# Updated_ADC.net
KiCad netlist of a schematic drawn in EAGLE
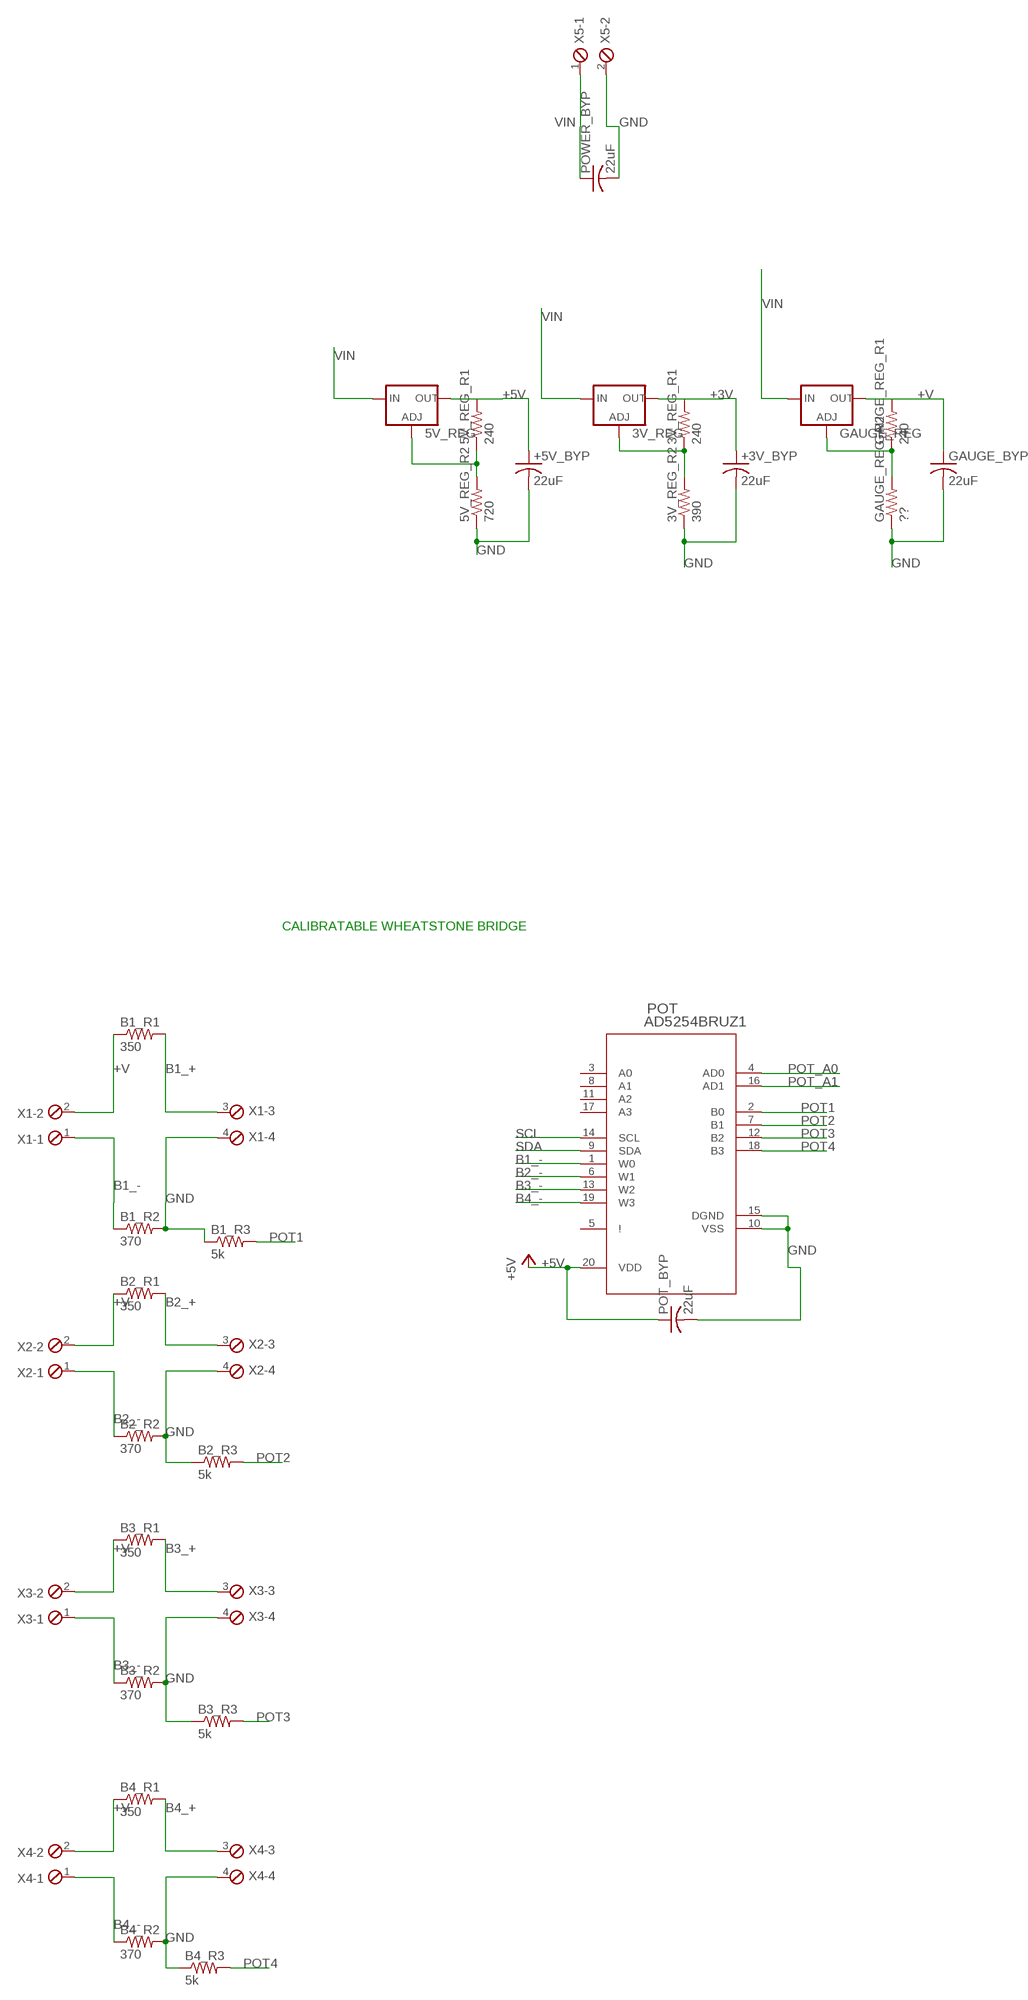
[diagram p0: schematic, sheet 1, part 1 of 2]
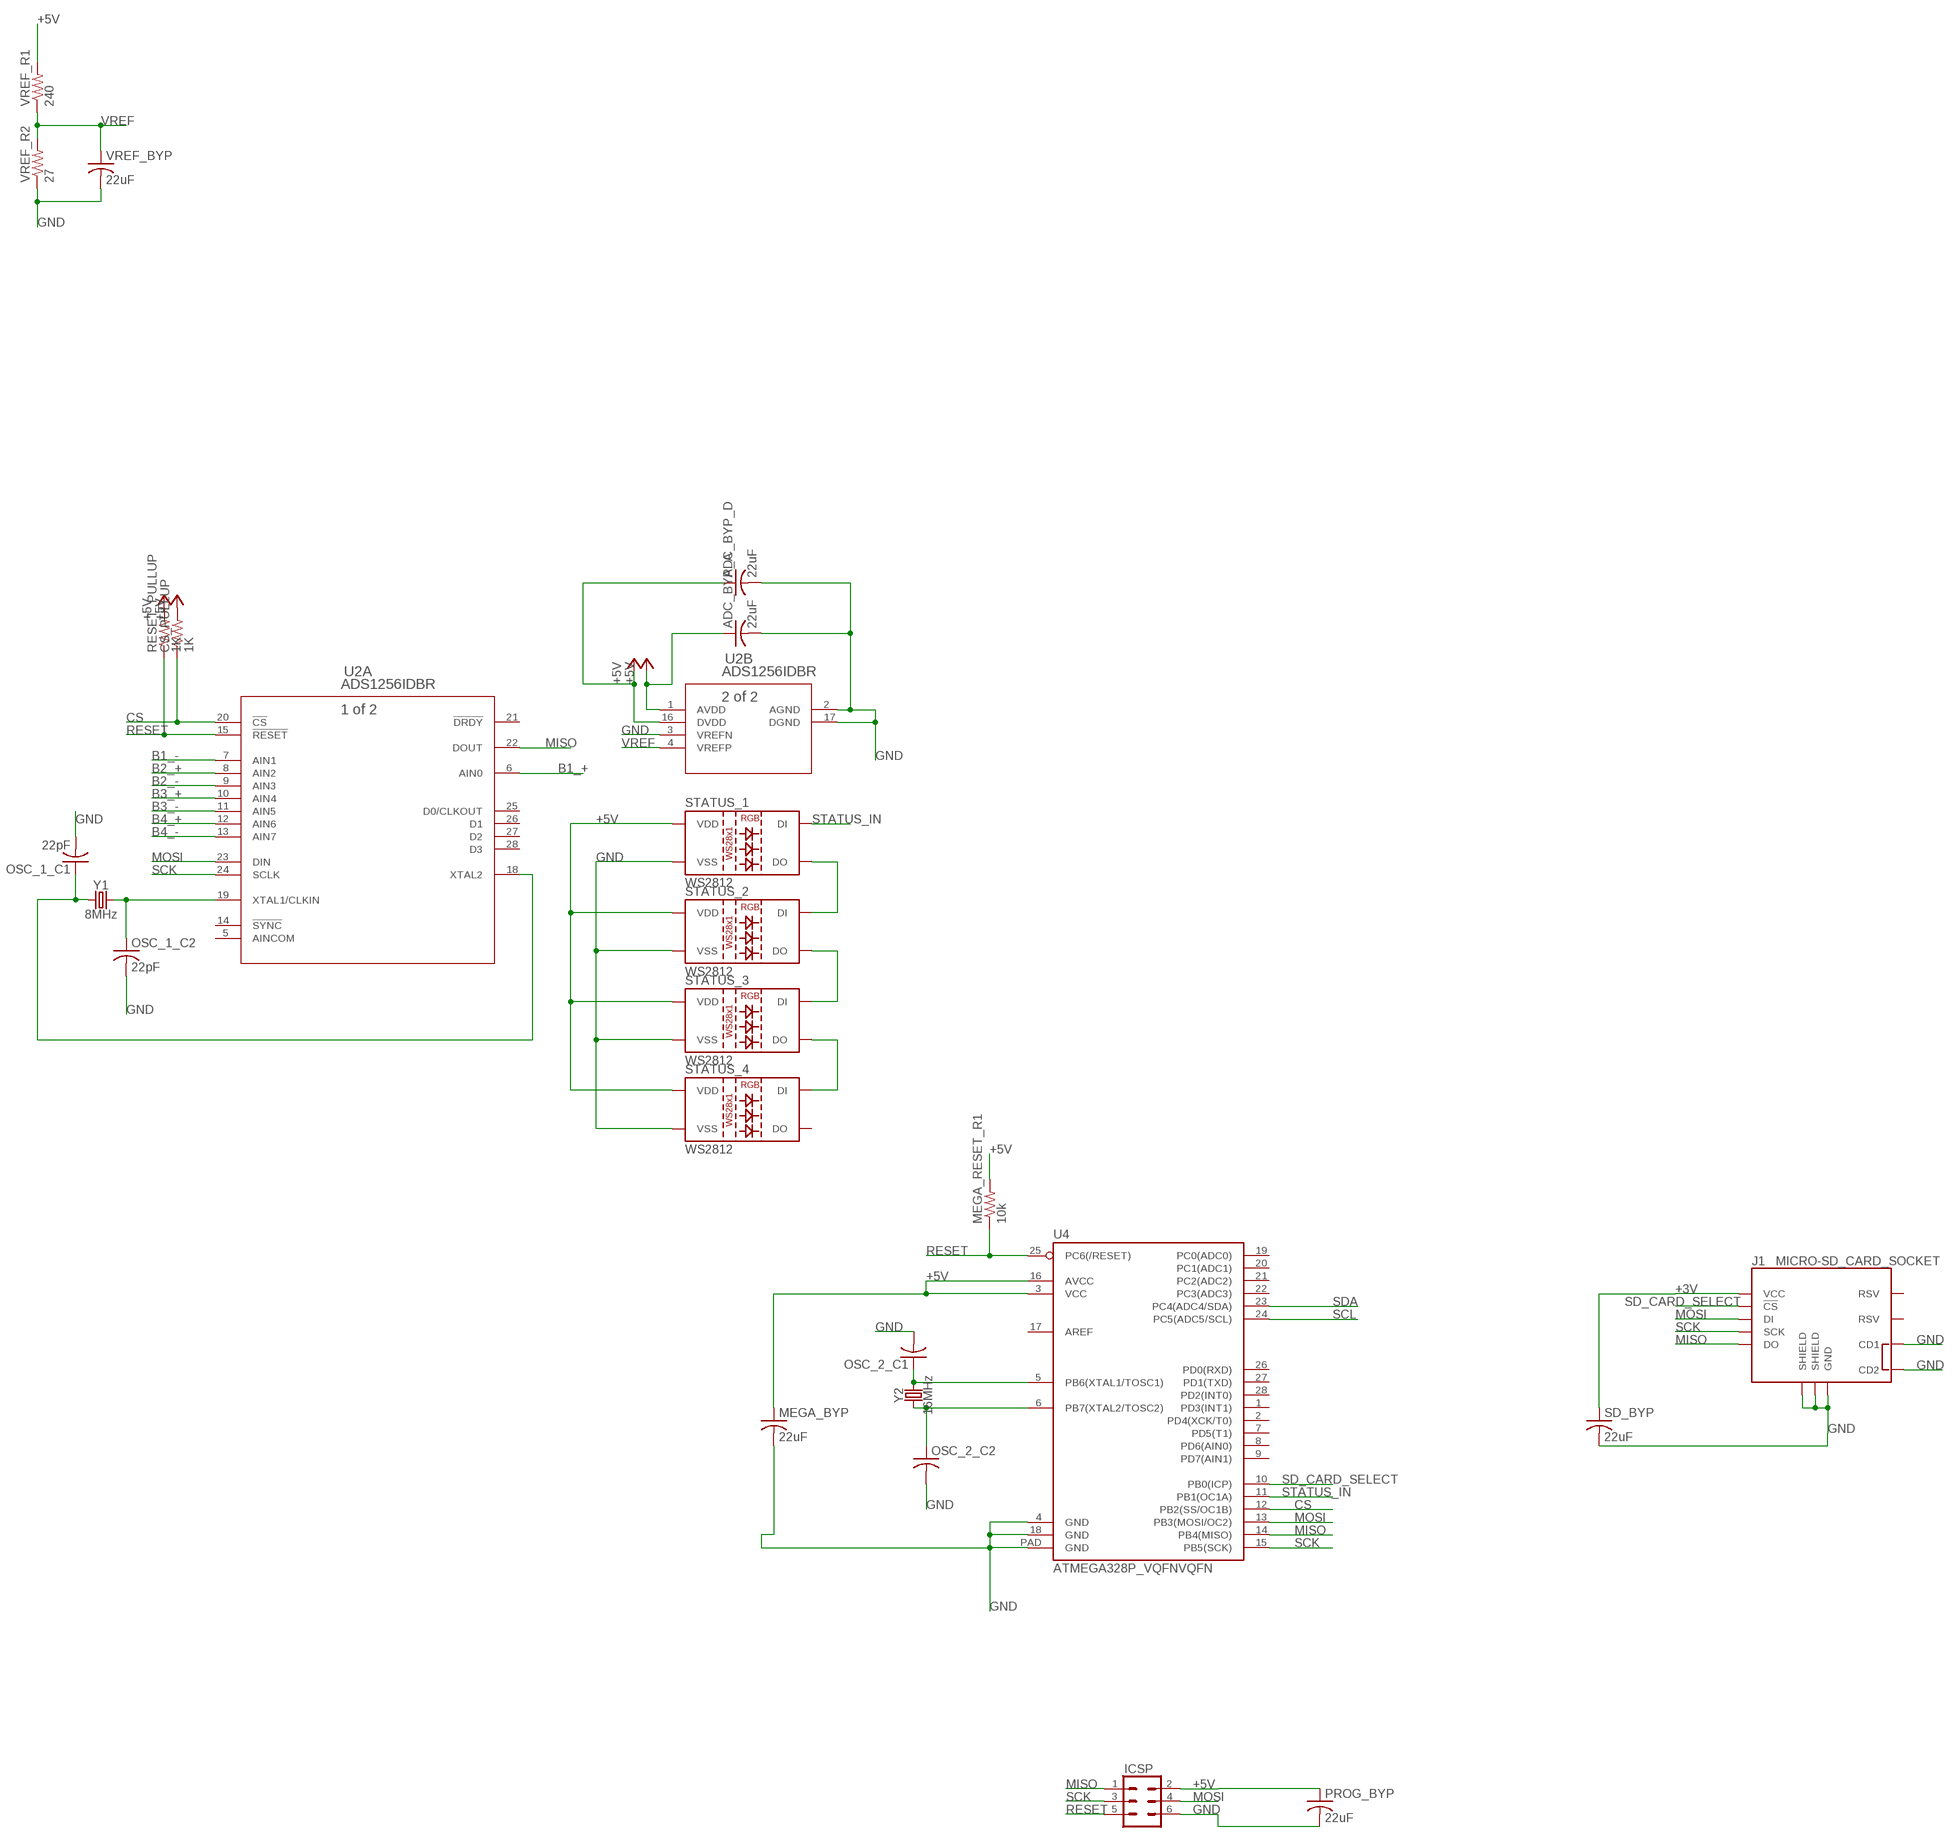
[diagram p1: schematic, sheet 1, part 2 of 2]

(export (version "E")
  (design (tool "Eeschema 10.0.6"))
  (components
    (comp (ref "+3V_BYP")
      (value "22uF")
      (footprint "eagle-import:C1206")
      (libsource (lib "eagle-import") (part "C-USC1206"))
    )
    (comp (ref "+5V_BYP")
      (value "22uF")
      (footprint "eagle-import:C1206")
      (libsource (lib "eagle-import") (part "C-USC1206"))
    )
    (comp (ref "3V_REG")
      (value "V_REG_317SMD")
      (footprint "eagle-import:SOT223")
      (libsource (lib "eagle-import") (part "V_REG_317SMD"))
    )
    (comp (ref "3V_REG_R1")
      (value "240")
      (footprint "eagle-import:R1206")
      (libsource (lib "eagle-import") (part "R-US_R1206"))
    )
    (comp (ref "3V_REG_R2")
      (value "390")
      (footprint "eagle-import:R1206")
      (libsource (lib "eagle-import") (part "R-US_R1206"))
    )
    (comp (ref "5V_REG")
      (value "V_REG_317SMD")
      (footprint "eagle-import:SOT223")
      (libsource (lib "eagle-import") (part "V_REG_317SMD"))
    )
    (comp (ref "5V_REG_R1")
      (value "240")
      (footprint "eagle-import:R1206")
      (libsource (lib "eagle-import") (part "R-US_R1206"))
    )
    (comp (ref "5V_REG_R2")
      (value "720")
      (footprint "eagle-import:R1206")
      (libsource (lib "eagle-import") (part "R-US_R1206"))
    )
    (comp (ref "ADC_BYP_A")
      (value "22uF")
      (footprint "eagle-import:C1206")
      (libsource (lib "eagle-import") (part "C-USC1206"))
    )
    (comp (ref "ADC_BYP_D")
      (value "22uF")
      (footprint "eagle-import:C1206")
      (libsource (lib "eagle-import") (part "C-USC1206"))
    )
    (comp (ref "B1_R1")
      (value "350")
      (footprint "eagle-import:R1206")
      (libsource (lib "eagle-import") (part "resistor_348_R-US_R1206"))
    )
    (comp (ref "B1_R2")
      (value "370")
      (footprint "eagle-import:R1206")
      (libsource (lib "eagle-import") (part "resistor_348_R-US_R1206"))
    )
    (comp (ref "B1_R3")
      (value "5k")
      (footprint "eagle-import:R1206")
      (libsource (lib "eagle-import") (part "resistor_348_R-US_R1206"))
    )
    (comp (ref "B2_R1")
      (value "350")
      (footprint "eagle-import:R1206")
      (libsource (lib "eagle-import") (part "resistor_348_R-US_R1206"))
    )
    (comp (ref "B2_R2")
      (value "370")
      (footprint "eagle-import:R1206")
      (libsource (lib "eagle-import") (part "resistor_348_R-US_R1206"))
    )
    (comp (ref "B2_R3")
      (value "5k")
      (footprint "eagle-import:R1206")
      (libsource (lib "eagle-import") (part "resistor_348_R-US_R1206"))
    )
    (comp (ref "B3_R1")
      (value "350")
      (footprint "eagle-import:R1206")
      (libsource (lib "eagle-import") (part "resistor_348_R-US_R1206"))
    )
    (comp (ref "B3_R2")
      (value "370")
      (footprint "eagle-import:R1206")
      (libsource (lib "eagle-import") (part "resistor_348_R-US_R1206"))
    )
    (comp (ref "B3_R3")
      (value "5k")
      (footprint "eagle-import:R1206")
      (libsource (lib "eagle-import") (part "resistor_348_R-US_R1206"))
    )
    (comp (ref "B4_R1")
      (value "350")
      (footprint "eagle-import:R1206")
      (libsource (lib "eagle-import") (part "resistor_348_R-US_R1206"))
    )
    (comp (ref "B4_R2")
      (value "370")
      (footprint "eagle-import:R1206")
      (libsource (lib "eagle-import") (part "resistor_348_R-US_R1206"))
    )
    (comp (ref "B4_R3")
      (value "5k")
      (footprint "eagle-import:R1206")
      (libsource (lib "eagle-import") (part "resistor_348_R-US_R1206"))
    )
    (comp (ref "CS_PULLUP")
      (value "1K")
      (footprint "eagle-import:M1206")
      (libsource (lib "eagle-import") (part "resistor_348_R-US_M1206"))
    )
    (comp (ref "GAUGE_BYP")
      (value "22uF")
      (footprint "eagle-import:C1206")
      (libsource (lib "eagle-import") (part "C-USC1206"))
    )
    (comp (ref "GAUGE_REG")
      (value "V_REG_317SMD")
      (footprint "eagle-import:SOT223")
      (libsource (lib "eagle-import") (part "V_REG_317SMD"))
    )
    (comp (ref "GAUGE_REG_R1")
      (value "240")
      (footprint "eagle-import:R1206")
      (libsource (lib "eagle-import") (part "R-US_R1206"))
    )
    (comp (ref "GAUGE_REG_R2")
      (value "??")
      (footprint "eagle-import:R1206")
      (libsource (lib "eagle-import") (part "R-US_R1206"))
    )
    (comp (ref "ICSP")
      (value "CONN_03X2FEMALE")
      (footprint "eagle-import:2X3")
      (libsource (lib "eagle-import") (part "CONN_03X2FEMALE"))
    )
    (comp (ref "J1")
      (value "MICRO-SD_CARD_SOCKET")
      (footprint "eagle-import:MICRO-SD-SOCKET")
      (libsource (lib "eagle-import") (part "MICRO-SD_CARD_SOCKET"))
    )
    (comp (ref "MEGA_BYP")
      (value "22uF")
      (footprint "eagle-import:C1206")
      (libsource (lib "eagle-import") (part "C-USC1206"))
    )
    (comp (ref "MEGA_RESET_R1")
      (value "10k")
      (footprint "eagle-import:M1206")
      (libsource (lib "eagle-import") (part "resistor_348_R-US_M1206"))
    )
    (comp (ref "OSC_1_C1")
      (value "22pF")
      (footprint "eagle-import:C1206")
      (libsource (lib "eagle-import") (part "C-USC1206"))
    )
    (comp (ref "OSC_1_C2")
      (value "22pF")
      (footprint "eagle-import:C1206")
      (libsource (lib "eagle-import") (part "C-USC1206"))
    )
    (comp (ref "OSC_2_C1")
      (value "C-USC1206")
      (footprint "eagle-import:C1206")
      (libsource (lib "eagle-import") (part "C-USC1206"))
    )
    (comp (ref "OSC_2_C2")
      (value "C-USC1206")
      (footprint "eagle-import:C1206")
      (libsource (lib "eagle-import") (part "C-USC1206"))
    )
    (comp (ref "POT")
      (value "AD5254BRUZ1")
      (footprint "eagle-import:RU_20")
      (libsource (lib "eagle-import") (part "AD5254BRUZ1"))
    )
    (comp (ref "POT_BYP")
      (value "22uF")
      (footprint "eagle-import:C1206")
      (libsource (lib "eagle-import") (part "C-USC1206"))
    )
    (comp (ref "POWER_BYP")
      (value "22uF")
      (footprint "eagle-import:C1206")
      (libsource (lib "eagle-import") (part "C-USC1206"))
    )
    (comp (ref "PROG_BYP")
      (value "22uF")
      (footprint "eagle-import:C1206")
      (libsource (lib "eagle-import") (part "C-USC1206"))
    )
    (comp (ref "RESET_PULLUP")
      (value "1K")
      (footprint "eagle-import:M1206")
      (libsource (lib "eagle-import") (part "resistor_348_R-US_M1206"))
    )
    (comp (ref "SD_BYP")
      (value "22uF")
      (footprint "eagle-import:C1206")
      (libsource (lib "eagle-import") (part "C-USC1206"))
    )
    (comp (ref "STATUS_1")
      (value "WS2812")
      (footprint "eagle-import:LED-TRICOLOR-5050-IC")
      (libsource (lib "eagle-import") (part "WS2812{dblquote}"))
    )
    (comp (ref "STATUS_2")
      (value "WS2812")
      (footprint "eagle-import:LED-TRICOLOR-5050-IC")
      (libsource (lib "eagle-import") (part "WS2812{dblquote}"))
    )
    (comp (ref "STATUS_3")
      (value "WS2812")
      (footprint "eagle-import:LED-TRICOLOR-5050-IC")
      (libsource (lib "eagle-import") (part "WS2812{dblquote}"))
    )
    (comp (ref "STATUS_4")
      (value "WS2812")
      (footprint "eagle-import:LED-TRICOLOR-5050-IC")
      (libsource (lib "eagle-import") (part "WS2812{dblquote}"))
    )
    (comp (ref "U2")
      (value "ADS1256IDBR")
      (footprint "eagle-import:DB28")
      (libsource (lib "eagle-import") (part "ADS1256IDBR"))
    )
    (comp (ref "U4")
      (value "ATMEGA328P_VQFNVQFN")
      (footprint "eagle-import:VQFN-28")
      (libsource (lib "eagle-import") (part "ATMEGA328P_VQFNVQFN"))
    )
    (comp (ref "VREF_BYP")
      (value "22uF")
      (footprint "eagle-import:C1206")
      (libsource (lib "eagle-import") (part "C-USC1206"))
    )
    (comp (ref "VREF_R1")
      (value "240")
      (footprint "eagle-import:R1206")
      (libsource (lib "eagle-import") (part "resistor_348_R-US_R1206"))
    )
    (comp (ref "VREF_R2")
      (value "27")
      (footprint "eagle-import:R1206")
      (libsource (lib "eagle-import") (part "resistor_348_R-US_R1206"))
    )
    (comp (ref "X1")
      (value "MPT4")
      (footprint "eagle-import:4POL254")
      (libsource (lib "eagle-import") (part "MPT4"))
    )
    (comp (ref "X2")
      (value "MPT4")
      (footprint "eagle-import:4POL254")
      (libsource (lib "eagle-import") (part "MPT4"))
    )
    (comp (ref "X3")
      (value "MPT4")
      (footprint "eagle-import:4POL254")
      (libsource (lib "eagle-import") (part "MPT4"))
    )
    (comp (ref "X4")
      (value "MPT4")
      (footprint "eagle-import:4POL254")
      (libsource (lib "eagle-import") (part "MPT4"))
    )
    (comp (ref "X5")
      (value "MPT2")
      (footprint "eagle-import:2POL254")
      (libsource (lib "eagle-import") (part "MPT2"))
    )
    (comp (ref "Y1")
      (value "8MHz")
      (footprint "eagle-import:CRYSTAL-SMD-5X3.2-4PAD")
      (libsource (lib "eagle-import") (part "CRYSTAL-8MHZSMD-5X3.2"))
    )
    (comp (ref "Y2")
      (value "16MHz")
      (footprint "eagle-import:CRYSTAL-SMD-5X3.2-4PAD")
      (libsource (lib "eagle-import") (part "CRYSTAL-8MHZSMD-5X3.2"))
    )
  )
  (nets
    (net (code "1") (name "+5V") (class "Default")
      (node (ref "+5V_BYP") (pin "1") (pinfunction "1_1") (pintype "passive"))
      (node (ref "5V_REG") (pin "2") (pinfunction "OUT_2") (pintype "output"))
      (node (ref "ADC_BYP_A") (pin "1") (pinfunction "1_1") (pintype "passive"))
      (node (ref "ADC_BYP_D") (pin "1") (pinfunction "1_1") (pintype "passive"))
      (node (ref "CS_PULLUP") (pin "2") (pinfunction "2_2") (pintype "passive"))
      (node (ref "ICSP") (pin "2") (pinfunction "2_2") (pintype "bidirectional"))
      (node (ref "MEGA_BYP") (pin "1") (pinfunction "1_1") (pintype "passive"))
      (node (ref "MEGA_RESET_R1") (pin "2") (pinfunction "2_2") (pintype "passive"))
      (node (ref "POT") (pin "20") (pinfunction "VDD_20") (pintype "power_in"))
      (node (ref "POT_BYP") (pin "1") (pinfunction "1_1") (pintype "passive"))
      (node (ref "PROG_BYP") (pin "1") (pinfunction "1_1") (pintype "passive"))
      (node (ref "RESET_PULLUP") (pin "2") (pinfunction "2_2") (pintype "passive"))
      (node (ref "STATUS_1") (pin "3") (pinfunction "VDD_3") (pintype "bidirectional"))
      (node (ref "STATUS_1") (pin "5") (pinfunction "VDD_5") (pintype "bidirectional"))
      (node (ref "STATUS_2") (pin "3") (pinfunction "VDD_3") (pintype "bidirectional"))
      (node (ref "STATUS_2") (pin "5") (pinfunction "VDD_5") (pintype "bidirectional"))
      (node (ref "STATUS_3") (pin "3") (pinfunction "VDD_3") (pintype "bidirectional"))
      (node (ref "STATUS_3") (pin "5") (pinfunction "VDD_5") (pintype "bidirectional"))
      (node (ref "STATUS_4") (pin "3") (pinfunction "VDD_3") (pintype "bidirectional"))
      (node (ref "STATUS_4") (pin "5") (pinfunction "VDD_5") (pintype "bidirectional"))
      (node (ref "U2") (pin "1") (pinfunction "AVDD_1") (pintype "passive"))
      (node (ref "U2") (pin "16") (pinfunction "DVDD_16") (pintype "power_in"))
      (node (ref "U4") (pin "16") (pinfunction "AVCC_16") (pintype "bidirectional"))
      (node (ref "U4") (pin "3") (pinfunction "VCC_3") (pintype "bidirectional"))
      (node (ref "VREF_R1") (pin "2") (pinfunction "2_2") (pintype "passive"))
    )
    (net (code "2") (name "/+3V") (class "Default")
      (node (ref "+3V_BYP") (pin "1") (pinfunction "1_1") (pintype "passive"))
      (node (ref "3V_REG") (pin "2") (pinfunction "OUT_2") (pintype "output"))
      (node (ref "J1") (pin "VCC") (pinfunction "VCC_VCC") (pintype "bidirectional"))
      (node (ref "SD_BYP") (pin "1") (pinfunction "1_1") (pintype "passive"))
    )
    (net (code "3") (name "/+V") (class "Default")
      (node (ref "B1_R1") (pin "1") (pinfunction "1_1") (pintype "passive"))
      (node (ref "B2_R1") (pin "1") (pinfunction "1_1") (pintype "passive"))
      (node (ref "B3_R1") (pin "1") (pinfunction "1_1") (pintype "passive"))
      (node (ref "B4_R1") (pin "1") (pinfunction "1_1") (pintype "passive"))
      (node (ref "GAUGE_BYP") (pin "1") (pinfunction "1_1") (pintype "passive"))
      (node (ref "GAUGE_REG") (pin "2") (pinfunction "OUT_2") (pintype "output"))
      (node (ref "X1") (pin "2") (pinfunction "1_2") (pintype "passive"))
      (node (ref "X2") (pin "2") (pinfunction "1_2") (pintype "passive"))
      (node (ref "X3") (pin "2") (pinfunction "1_2") (pintype "passive"))
      (node (ref "X4") (pin "2") (pinfunction "1_2") (pintype "passive"))
    )
    (net (code "4") (name "/B1_+") (class "Default")
      (node (ref "B1_R1") (pin "2") (pinfunction "2_2") (pintype "passive"))
      (node (ref "U2") (pin "6") (pinfunction "AIN0_6") (pintype "passive"))
      (node (ref "X1") (pin "3") (pinfunction "1_3") (pintype "passive"))
    )
    (net (code "5") (name "/B1_-") (class "Default")
      (node (ref "B1_R2") (pin "1") (pinfunction "1_1") (pintype "passive"))
      (node (ref "POT") (pin "1") (pinfunction "W0_1") (pintype "passive"))
      (node (ref "U2") (pin "7") (pinfunction "AIN1_7") (pintype "passive"))
      (node (ref "X1") (pin "1") (pinfunction "1_1") (pintype "passive"))
    )
    (net (code "6") (name "/B2_+") (class "Default")
      (node (ref "B2_R1") (pin "2") (pinfunction "2_2") (pintype "passive"))
      (node (ref "U2") (pin "8") (pinfunction "AIN2_8") (pintype "passive"))
      (node (ref "X2") (pin "3") (pinfunction "1_3") (pintype "passive"))
    )
    (net (code "7") (name "/B2_-") (class "Default")
      (node (ref "B2_R2") (pin "1") (pinfunction "1_1") (pintype "passive"))
      (node (ref "POT") (pin "6") (pinfunction "W1_6") (pintype "passive"))
      (node (ref "U2") (pin "9") (pinfunction "AIN3_9") (pintype "passive"))
      (node (ref "X2") (pin "1") (pinfunction "1_1") (pintype "passive"))
    )
    (net (code "8") (name "/B3_+") (class "Default")
      (node (ref "B3_R1") (pin "2") (pinfunction "2_2") (pintype "passive"))
      (node (ref "U2") (pin "10") (pinfunction "AIN4_10") (pintype "passive"))
      (node (ref "X3") (pin "3") (pinfunction "1_3") (pintype "passive"))
    )
    (net (code "9") (name "/B3_-") (class "Default")
      (node (ref "B3_R2") (pin "1") (pinfunction "1_1") (pintype "passive"))
      (node (ref "POT") (pin "13") (pinfunction "W2_13") (pintype "passive"))
      (node (ref "U2") (pin "11") (pinfunction "AIN5_11") (pintype "passive"))
      (node (ref "X3") (pin "1") (pinfunction "1_1") (pintype "passive"))
    )
    (net (code "10") (name "/B4_+") (class "Default")
      (node (ref "B4_R1") (pin "2") (pinfunction "2_2") (pintype "passive"))
      (node (ref "U2") (pin "12") (pinfunction "AIN6_12") (pintype "passive"))
      (node (ref "X4") (pin "3") (pinfunction "1_3") (pintype "passive"))
    )
    (net (code "11") (name "/B4_-") (class "Default")
      (node (ref "B4_R2") (pin "1") (pinfunction "1_1") (pintype "passive"))
      (node (ref "POT") (pin "19") (pinfunction "W3_19") (pintype "passive"))
      (node (ref "U2") (pin "13") (pinfunction "AIN7_13") (pintype "passive"))
      (node (ref "X4") (pin "1") (pinfunction "1_1") (pintype "passive"))
    )
    (net (code "12") (name "/CS") (class "Default")
      (node (ref "CS_PULLUP") (pin "1") (pinfunction "1_1") (pintype "passive"))
      (node (ref "U2") (pin "20") (pinfunction "~{CS}_20") (pintype "input"))
      (node (ref "U4") (pin "12") (pinfunction "PB2(SS/OC1B)_12") (pintype "bidirectional"))
    )
    (net (code "13") (name "/GND") (class "Default")
      (node (ref "+3V_BYP") (pin "2") (pinfunction "2_2") (pintype "passive"))
      (node (ref "+5V_BYP") (pin "2") (pinfunction "2_2") (pintype "passive"))
      (node (ref "3V_REG_R2") (pin "1") (pinfunction "1_1") (pintype "passive"))
      (node (ref "5V_REG_R2") (pin "1") (pinfunction "1_1") (pintype "passive"))
      (node (ref "ADC_BYP_A") (pin "2") (pinfunction "2_2") (pintype "passive"))
      (node (ref "ADC_BYP_D") (pin "2") (pinfunction "2_2") (pintype "passive"))
      (node (ref "B1_R2") (pin "2") (pinfunction "2_2") (pintype "passive"))
      (node (ref "B1_R3") (pin "1") (pinfunction "1_1") (pintype "passive"))
      (node (ref "B2_R2") (pin "2") (pinfunction "2_2") (pintype "passive"))
      (node (ref "B2_R3") (pin "1") (pinfunction "1_1") (pintype "passive"))
      (node (ref "B3_R2") (pin "2") (pinfunction "2_2") (pintype "passive"))
      (node (ref "B3_R3") (pin "1") (pinfunction "1_1") (pintype "passive"))
      (node (ref "B4_R2") (pin "2") (pinfunction "2_2") (pintype "passive"))
      (node (ref "B4_R3") (pin "1") (pinfunction "1_1") (pintype "passive"))
      (node (ref "GAUGE_BYP") (pin "2") (pinfunction "2_2") (pintype "passive"))
      (node (ref "GAUGE_REG_R2") (pin "1") (pinfunction "1_1") (pintype "passive"))
      (node (ref "ICSP") (pin "6") (pinfunction "6_6") (pintype "bidirectional"))
      (node (ref "J1") (pin "CD1") (pinfunction "CD1_CD1") (pintype "bidirectional"))
      (node (ref "J1") (pin "CD2") (pinfunction "CD2_CD2") (pintype "bidirectional"))
      (node (ref "J1") (pin "GND") (pinfunction "GND_GND") (pintype "bidirectional"))
      (node (ref "J1") (pin "GND1") (pinfunction "SHIELD_GND1") (pintype "bidirectional"))
      (node (ref "J1") (pin "GND3") (pinfunction "SHIELD_GND3") (pintype "bidirectional"))
      (node (ref "MEGA_BYP") (pin "2") (pinfunction "2_2") (pintype "passive"))
      (node (ref "OSC_1_C1") (pin "2") (pinfunction "2_2") (pintype "passive"))
      (node (ref "OSC_1_C2") (pin "2") (pinfunction "2_2") (pintype "passive"))
      (node (ref "OSC_2_C1") (pin "2") (pinfunction "2_2") (pintype "passive"))
      (node (ref "OSC_2_C2") (pin "2") (pinfunction "2_2") (pintype "passive"))
      (node (ref "POT") (pin "10") (pinfunction "VSS_10") (pintype "power_in"))
      (node (ref "POT") (pin "15") (pinfunction "DGND_15") (pintype "passive"))
      (node (ref "POT_BYP") (pin "2") (pinfunction "2_2") (pintype "passive"))
      (node (ref "POWER_BYP") (pin "2") (pinfunction "2_2") (pintype "passive"))
      (node (ref "PROG_BYP") (pin "2") (pinfunction "2_2") (pintype "passive"))
      (node (ref "SD_BYP") (pin "2") (pinfunction "2_2") (pintype "passive"))
      (node (ref "STATUS_1") (pin "6") (pinfunction "VSS_6") (pintype "bidirectional"))
      (node (ref "STATUS_2") (pin "6") (pinfunction "VSS_6") (pintype "bidirectional"))
      (node (ref "STATUS_3") (pin "6") (pinfunction "VSS_6") (pintype "bidirectional"))
      (node (ref "STATUS_4") (pin "6") (pinfunction "VSS_6") (pintype "bidirectional"))
      (node (ref "U2") (pin "17") (pinfunction "DGND_17") (pintype "power_in"))
      (node (ref "U2") (pin "2") (pinfunction "AGND_2") (pintype "passive"))
      (node (ref "U2") (pin "3") (pinfunction "VREFN_3") (pintype "passive"))
      (node (ref "U4") (pin "18") (pinfunction "GND_18") (pintype "bidirectional"))
      (node (ref "U4") (pin "4") (pinfunction "GND_4") (pintype "bidirectional"))
      (node (ref "U4") (pin "PAD") (pinfunction "GND_PAD") (pintype "bidirectional"))
      (node (ref "VREF_BYP") (pin "2") (pinfunction "2_2") (pintype "passive"))
      (node (ref "VREF_R2") (pin "1") (pinfunction "1_1") (pintype "passive"))
      (node (ref "X1") (pin "4") (pinfunction "1_4") (pintype "passive"))
      (node (ref "X2") (pin "4") (pinfunction "1_4") (pintype "passive"))
      (node (ref "X3") (pin "4") (pinfunction "1_4") (pintype "passive"))
      (node (ref "X4") (pin "4") (pinfunction "1_4") (pintype "passive"))
      (node (ref "X5") (pin "2") (pinfunction "1_2") (pintype "passive"))
    )
    (net (code "14") (name "/MISO") (class "Default")
      (node (ref "ICSP") (pin "1") (pinfunction "1_1") (pintype "bidirectional"))
      (node (ref "J1") (pin "DO") (pinfunction "DO_DO") (pintype "bidirectional"))
      (node (ref "U2") (pin "22") (pinfunction "DOUT_22") (pintype "output"))
      (node (ref "U4") (pin "14") (pinfunction "PB4(MISO)_14") (pintype "bidirectional"))
    )
    (net (code "15") (name "/MOSI") (class "Default")
      (node (ref "ICSP") (pin "4") (pinfunction "4_4") (pintype "bidirectional"))
      (node (ref "J1") (pin "DI") (pinfunction "DI_DI") (pintype "bidirectional"))
      (node (ref "U2") (pin "23") (pinfunction "DIN_23") (pintype "input"))
      (node (ref "U4") (pin "13") (pinfunction "PB3(MOSI/OC2)_13") (pintype "bidirectional"))
    )
    (net (code "16") (name "/POT1") (class "Default")
      (node (ref "B1_R3") (pin "2") (pinfunction "2_2") (pintype "passive"))
      (node (ref "POT") (pin "2") (pinfunction "B0_2") (pintype "passive"))
    )
    (net (code "17") (name "/POT2") (class "Default")
      (node (ref "B2_R3") (pin "2") (pinfunction "2_2") (pintype "passive"))
      (node (ref "POT") (pin "7") (pinfunction "B1_7") (pintype "passive"))
    )
    (net (code "18") (name "/POT3") (class "Default")
      (node (ref "B3_R3") (pin "2") (pinfunction "2_2") (pintype "passive"))
      (node (ref "POT") (pin "12") (pinfunction "B2_12") (pintype "passive"))
    )
    (net (code "19") (name "/POT4") (class "Default")
      (node (ref "B4_R3") (pin "2") (pinfunction "2_2") (pintype "passive"))
      (node (ref "POT") (pin "18") (pinfunction "B3_18") (pintype "passive"))
    )
    (net (code "20") (name "/POT_A0") (class "Default")
      (node (ref "POT") (pin "4") (pinfunction "AD0_4") (pintype "passive"))
    )
    (net (code "21") (name "/POT_A1") (class "Default")
      (node (ref "POT") (pin "16") (pinfunction "AD1_16") (pintype "passive"))
    )
    (net (code "22") (name "/RESET") (class "Default")
      (node (ref "ICSP") (pin "5") (pinfunction "5_5") (pintype "bidirectional"))
      (node (ref "MEGA_RESET_R1") (pin "1") (pinfunction "1_1") (pintype "passive"))
      (node (ref "RESET_PULLUP") (pin "1") (pinfunction "1_1") (pintype "passive"))
      (node (ref "U2") (pin "15") (pinfunction "~{RESET}_15") (pintype "input"))
      (node (ref "U4") (pin "25") (pinfunction "PC6(/RESET)_25") (pintype "bidirectional"))
    )
    (net (code "23") (name "/SCK") (class "Default")
      (node (ref "ICSP") (pin "3") (pinfunction "3_3") (pintype "bidirectional"))
      (node (ref "J1") (pin "SCLK") (pinfunction "SCK_SCLK") (pintype "bidirectional"))
      (node (ref "U2") (pin "24") (pinfunction "SCLK_24") (pintype "input"))
      (node (ref "U4") (pin "15") (pinfunction "PB5(SCK)_15") (pintype "bidirectional"))
    )
    (net (code "24") (name "/SCL") (class "Default")
      (node (ref "POT") (pin "14") (pinfunction "SCL_14") (pintype "passive"))
      (node (ref "U4") (pin "24") (pinfunction "PC5(ADC5/SCL)_24") (pintype "bidirectional"))
    )
    (net (code "25") (name "/SDA") (class "Default")
      (node (ref "POT") (pin "9") (pinfunction "SDA_9") (pintype "passive"))
      (node (ref "U4") (pin "23") (pinfunction "PC4(ADC4/SDA)_23") (pintype "bidirectional"))
    )
    (net (code "26") (name "/SD_CARD_SELECT") (class "Default")
      (node (ref "J1") (pin "CS") (pinfunction "~{CS}_CS") (pintype "bidirectional"))
      (node (ref "U4") (pin "10") (pinfunction "PB0(ICP)_10") (pintype "bidirectional"))
    )
    (net (code "27") (name "/STATUS_IN") (class "Default")
      (node (ref "STATUS_1") (pin "2") (pinfunction "DI_2") (pintype "bidirectional"))
      (node (ref "U4") (pin "11") (pinfunction "PB1(OC1A)_11") (pintype "bidirectional"))
    )
    (net (code "28") (name "/VIN") (class "Default")
      (node (ref "3V_REG") (pin "3") (pinfunction "IN_3") (pintype "input"))
      (node (ref "5V_REG") (pin "3") (pinfunction "IN_3") (pintype "input"))
      (node (ref "GAUGE_REG") (pin "3") (pinfunction "IN_3") (pintype "input"))
      (node (ref "POWER_BYP") (pin "1") (pinfunction "1_1") (pintype "passive"))
      (node (ref "X5") (pin "1") (pinfunction "1_1") (pintype "passive"))
    )
    (net (code "29") (name "/VREF") (class "Default")
      (node (ref "U2") (pin "4") (pinfunction "VREFP_4") (pintype "passive"))
      (node (ref "VREF_BYP") (pin "1") (pinfunction "1_1") (pintype "passive"))
      (node (ref "VREF_R1") (pin "1") (pinfunction "1_1") (pintype "passive"))
      (node (ref "VREF_R2") (pin "2") (pinfunction "2_2") (pintype "passive"))
    )
    (net (code "30") (name "Net-(3V_REG-ADJ)") (class "Default")
      (node (ref "3V_REG") (pin "1") (pinfunction "ADJ_1") (pintype "input"))
      (node (ref "3V_REG_R1") (pin "1") (pinfunction "1_1") (pintype "passive"))
      (node (ref "3V_REG_R2") (pin "2") (pinfunction "2_2") (pintype "passive"))
    )
    (net (code "31") (name "Net-(5V_REG-ADJ)") (class "Default")
      (node (ref "5V_REG") (pin "1") (pinfunction "ADJ_1") (pintype "input"))
      (node (ref "5V_REG_R1") (pin "1") (pinfunction "1_1") (pintype "passive"))
      (node (ref "5V_REG_R2") (pin "2") (pinfunction "2_2") (pintype "passive"))
    )
    (net (code "32") (name "Net-(GAUGE_REG-ADJ)") (class "Default")
      (node (ref "GAUGE_REG") (pin "1") (pinfunction "ADJ_1") (pintype "input"))
      (node (ref "GAUGE_REG_R1") (pin "1") (pinfunction "1_1") (pintype "passive"))
      (node (ref "GAUGE_REG_R2") (pin "2") (pinfunction "2_2") (pintype "passive"))
    )
    (net (code "33") (name "Net-(STATUS_1-DO)") (class "Default")
      (node (ref "STATUS_1") (pin "1") (pinfunction "DO_1") (pintype "bidirectional"))
      (node (ref "STATUS_2") (pin "2") (pinfunction "DI_2") (pintype "bidirectional"))
    )
    (net (code "34") (name "Net-(STATUS_2-DO)") (class "Default")
      (node (ref "STATUS_2") (pin "1") (pinfunction "DO_1") (pintype "bidirectional"))
      (node (ref "STATUS_3") (pin "2") (pinfunction "DI_2") (pintype "bidirectional"))
    )
    (net (code "35") (name "Net-(STATUS_3-DO)") (class "Default")
      (node (ref "STATUS_3") (pin "1") (pinfunction "DO_1") (pintype "bidirectional"))
      (node (ref "STATUS_4") (pin "2") (pinfunction "DI_2") (pintype "bidirectional"))
    )
    (net (code "36") (name "Net-(U2A-XTAL1{slash}CLKIN)") (class "Default")
      (node (ref "OSC_1_C2") (pin "1") (pinfunction "1_1") (pintype "passive"))
      (node (ref "U2") (pin "19") (pinfunction "XTAL1/CLKIN_19") (pintype "input"))
      (node (ref "Y1") (pin "3") (pinfunction "2_3") (pintype "passive"))
    )
    (net (code "37") (name "Net-(U2A-XTAL2)") (class "Default")
      (node (ref "OSC_1_C1") (pin "1") (pinfunction "1_1") (pintype "passive"))
      (node (ref "U2") (pin "18") (pinfunction "XTAL2_18") (pintype "passive"))
      (node (ref "Y1") (pin "1") (pinfunction "1_1") (pintype "passive"))
    )
    (net (code "38") (name "Net-(U4-PB6(XTAL1{slash}TOSC1))") (class "Default")
      (node (ref "OSC_2_C1") (pin "1") (pinfunction "1_1") (pintype "passive"))
      (node (ref "U4") (pin "5") (pinfunction "PB6(XTAL1/TOSC1)_5") (pintype "bidirectional"))
      (node (ref "Y2") (pin "3") (pinfunction "2_3") (pintype "passive"))
    )
    (net (code "39") (name "Net-(U4-PB7(XTAL2{slash}TOSC2))") (class "Default")
      (node (ref "OSC_2_C2") (pin "1") (pinfunction "1_1") (pintype "passive"))
      (node (ref "U4") (pin "6") (pinfunction "PB7(XTAL2/TOSC2)_6") (pintype "bidirectional"))
      (node (ref "Y2") (pin "1") (pinfunction "1_1") (pintype "passive"))
    )
    (net (code "40") (name "unconnected-(3V_REG_R1-Pad2)") (class "Default")
      (node (ref "3V_REG_R1") (pin "2") (pinfunction "2_2") (pintype "passive"))
    )
    (net (code "41") (name "unconnected-(5V_REG_R1-Pad2)") (class "Default")
      (node (ref "5V_REG_R1") (pin "2") (pinfunction "2_2") (pintype "passive"))
    )
    (net (code "42") (name "unconnected-(GAUGE_REG_R1-Pad2)") (class "Default")
      (node (ref "GAUGE_REG_R1") (pin "2") (pinfunction "2_2") (pintype "passive"))
    )
    (net (code "43") (name "unconnected-(J1-RSV-PadRSV1)") (class "Default")
      (node (ref "J1") (pin "RSV1") (pinfunction "RSV_RSV1") (pintype "bidirectional"))
    )
    (net (code "44") (name "unconnected-(J1-RSV-PadRSV2)") (class "Default")
      (node (ref "J1") (pin "RSV2") (pinfunction "RSV_RSV2") (pintype "bidirectional"))
    )
    (net (code "45") (name "unconnected-(POT-A0-Pad3)") (class "Default")
      (node (ref "POT") (pin "3") (pinfunction "A0_3") (pintype "passive"))
    )
    (net (code "46") (name "unconnected-(POT-A1-Pad8)") (class "Default")
      (node (ref "POT") (pin "8") (pinfunction "A1_8") (pintype "passive"))
    )
    (net (code "47") (name "unconnected-(POT-A2-Pad11)") (class "Default")
      (node (ref "POT") (pin "11") (pinfunction "A2_11") (pintype "passive"))
    )
    (net (code "48") (name "unconnected-(POT-A3-Pad17)") (class "Default")
      (node (ref "POT") (pin "17") (pinfunction "A3_17") (pintype "passive"))
    )
    (net (code "49") (name "unconnected-(POT-~-Pad5)") (class "Default")
      (node (ref "POT") (pin "5") (pinfunction "~_5") (pintype "passive"))
    )
    (net (code "50") (name "unconnected-(STATUS_4-DO-Pad1)") (class "Default")
      (node (ref "STATUS_4") (pin "1") (pinfunction "DO_1") (pintype "bidirectional"))
    )
    (net (code "51") (name "unconnected-(U2A-AINCOM-Pad5)") (class "Default")
      (node (ref "U2") (pin "5") (pinfunction "AINCOM_5") (pintype "passive"))
    )
    (net (code "52") (name "unconnected-(U2A-D0{slash}CLKOUT-Pad25)") (class "Default")
      (node (ref "U2") (pin "25") (pinfunction "D0/CLKOUT_25") (pintype "passive"))
    )
    (net (code "53") (name "unconnected-(U2A-D1-Pad26)") (class "Default")
      (node (ref "U2") (pin "26") (pinfunction "D1_26") (pintype "passive"))
    )
    (net (code "54") (name "unconnected-(U2A-D2-Pad27)") (class "Default")
      (node (ref "U2") (pin "27") (pinfunction "D2_27") (pintype "passive"))
    )
    (net (code "55") (name "unconnected-(U2A-D3-Pad28)") (class "Default")
      (node (ref "U2") (pin "28") (pinfunction "D3_28") (pintype "passive"))
    )
    (net (code "56") (name "unconnected-(U2A-~{DRDY}-Pad21)") (class "Default")
      (node (ref "U2") (pin "21") (pinfunction "~{DRDY}_21") (pintype "output"))
    )
    (net (code "57") (name "unconnected-(U2A-~{SYNC}-Pad14)") (class "Default")
      (node (ref "U2") (pin "14") (pinfunction "~{SYNC}_14") (pintype "passive"))
    )
    (net (code "58") (name "unconnected-(U4-AREF-Pad17)") (class "Default")
      (node (ref "U4") (pin "17") (pinfunction "AREF_17") (pintype "bidirectional"))
    )
    (net (code "59") (name "unconnected-(U4-PC0(ADC0)-Pad19)") (class "Default")
      (node (ref "U4") (pin "19") (pinfunction "PC0(ADC0)_19") (pintype "bidirectional"))
    )
    (net (code "60") (name "unconnected-(U4-PC1(ADC1)-Pad20)") (class "Default")
      (node (ref "U4") (pin "20") (pinfunction "PC1(ADC1)_20") (pintype "bidirectional"))
    )
    (net (code "61") (name "unconnected-(U4-PC2(ADC2)-Pad21)") (class "Default")
      (node (ref "U4") (pin "21") (pinfunction "PC2(ADC2)_21") (pintype "bidirectional"))
    )
    (net (code "62") (name "unconnected-(U4-PC3(ADC3)-Pad22)") (class "Default")
      (node (ref "U4") (pin "22") (pinfunction "PC3(ADC3)_22") (pintype "bidirectional"))
    )
    (net (code "63") (name "unconnected-(U4-PD0(RXD)-Pad26)") (class "Default")
      (node (ref "U4") (pin "26") (pinfunction "PD0(RXD)_26") (pintype "bidirectional"))
    )
    (net (code "64") (name "unconnected-(U4-PD1(TXD)-Pad27)") (class "Default")
      (node (ref "U4") (pin "27") (pinfunction "PD1(TXD)_27") (pintype "bidirectional"))
    )
    (net (code "65") (name "unconnected-(U4-PD2(INT0)-Pad28)") (class "Default")
      (node (ref "U4") (pin "28") (pinfunction "PD2(INT0)_28") (pintype "bidirectional"))
    )
    (net (code "66") (name "unconnected-(U4-PD3(INT1)-Pad1)") (class "Default")
      (node (ref "U4") (pin "1") (pinfunction "PD3(INT1)_1") (pintype "bidirectional"))
    )
    (net (code "67") (name "unconnected-(U4-PD4(XCK{slash}T0)-Pad2)") (class "Default")
      (node (ref "U4") (pin "2") (pinfunction "PD4(XCK/T0)_2") (pintype "bidirectional"))
    )
    (net (code "68") (name "unconnected-(U4-PD5(T1)-Pad7)") (class "Default")
      (node (ref "U4") (pin "7") (pinfunction "PD5(T1)_7") (pintype "bidirectional"))
    )
    (net (code "69") (name "unconnected-(U4-PD6(AIN0)-Pad8)") (class "Default")
      (node (ref "U4") (pin "8") (pinfunction "PD6(AIN0)_8") (pintype "bidirectional"))
    )
    (net (code "70") (name "unconnected-(U4-PD7(AIN1)-Pad9)") (class "Default")
      (node (ref "U4") (pin "9") (pinfunction "PD7(AIN1)_9") (pintype "bidirectional"))
    )
  )
)
